# WaterMonitorV7_1.net
KiCad netlist of a schematic drawn in EAGLE
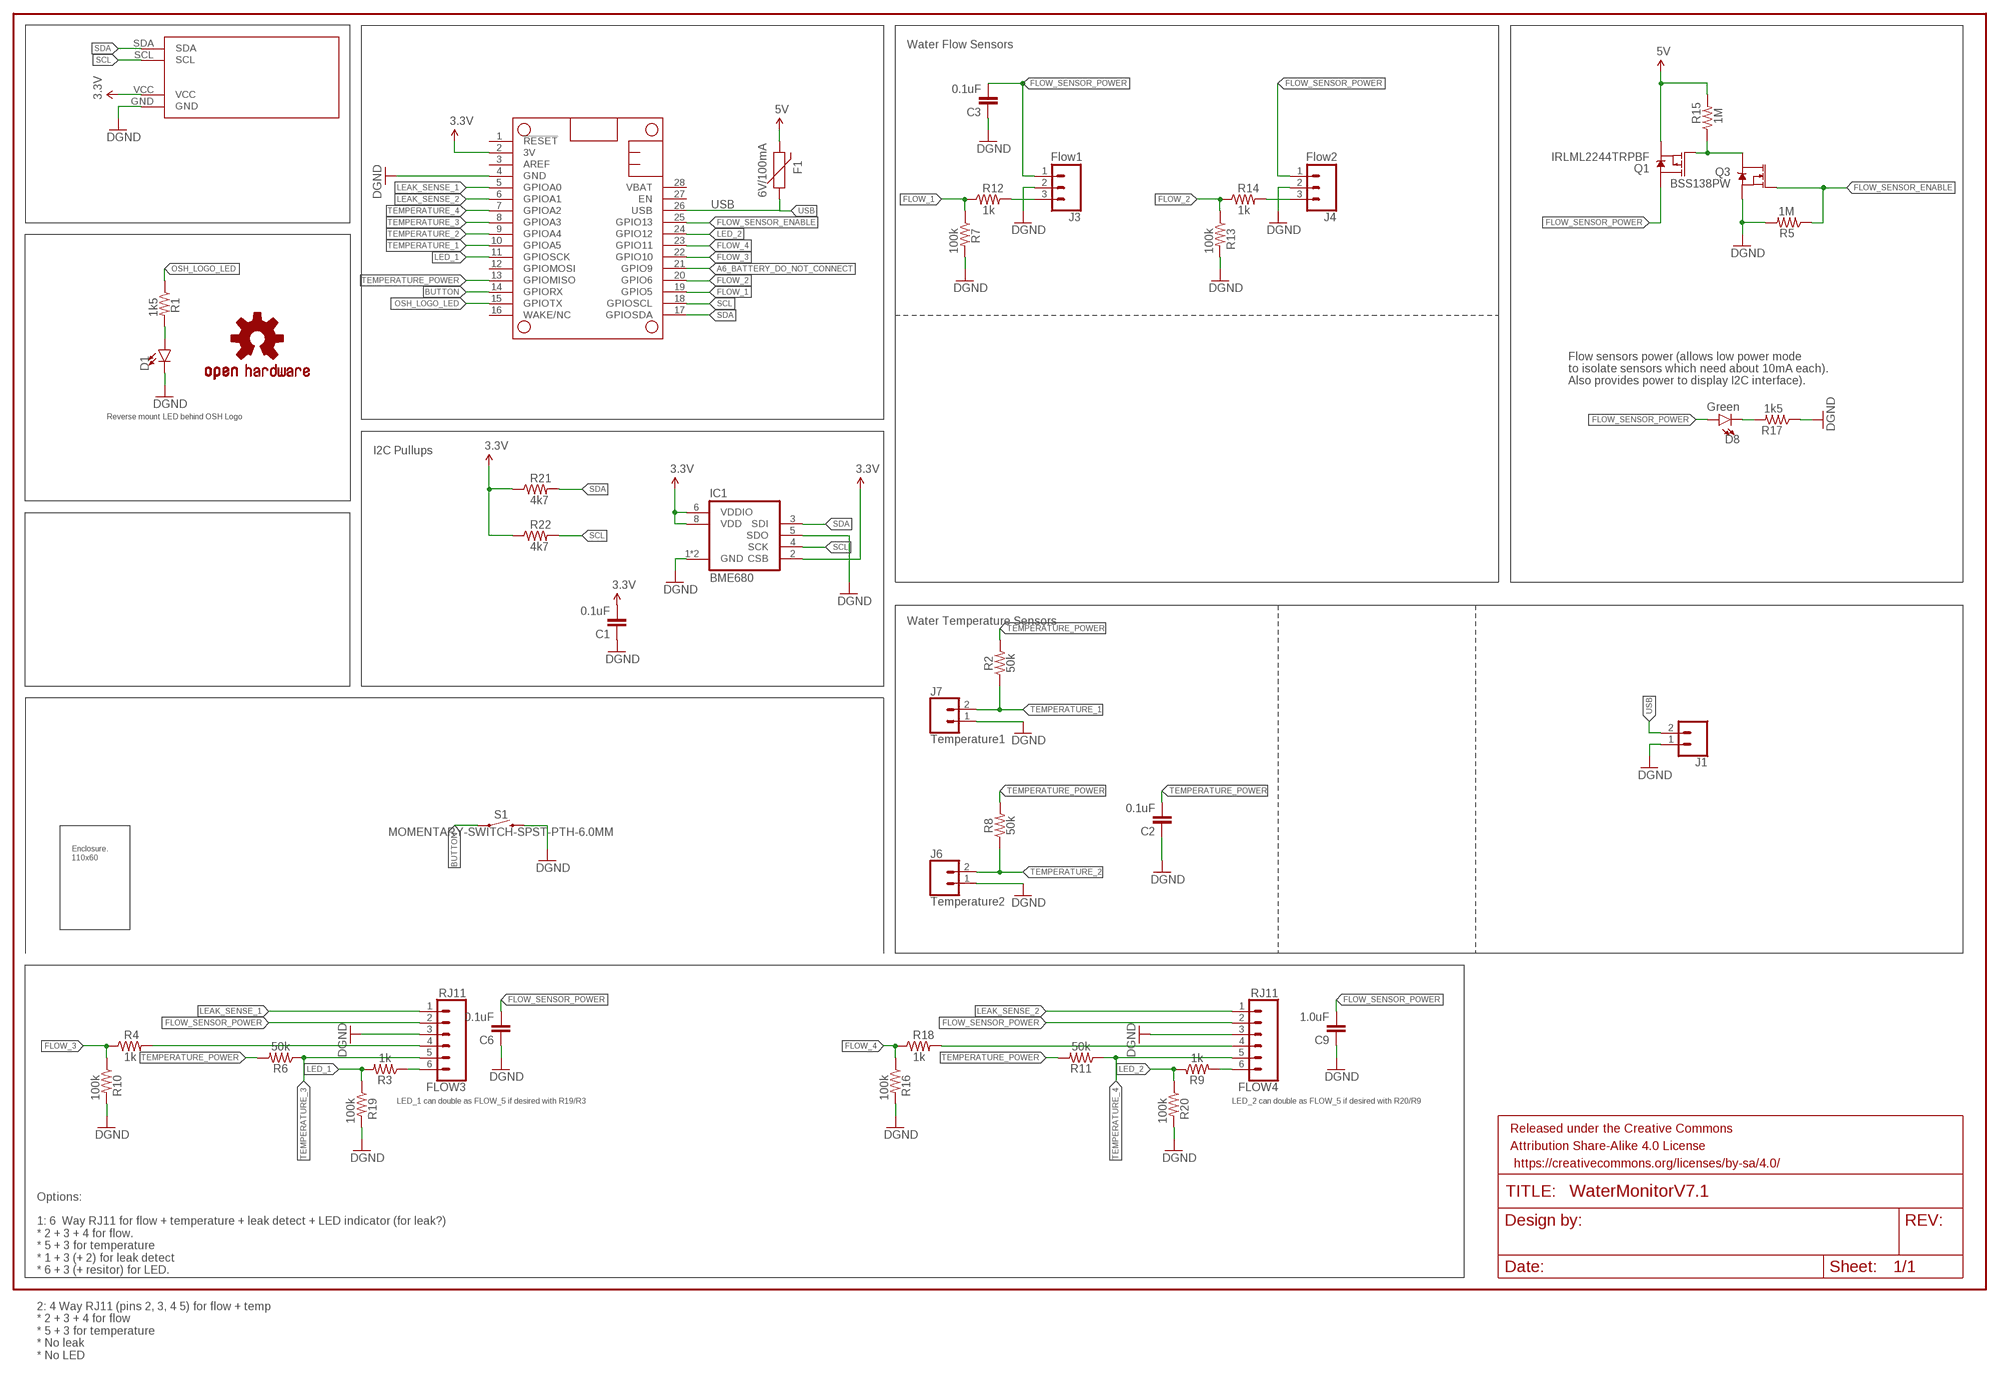
[diagram p0: schematic, sheet 1]

(export (version "E")
  (design (tool "Eeschema 10.0.6"))
  (components
    (comp (ref "C1")
      (value "0.1uF")
      (footprint "eagle-import:0805")
      (libsource (lib "eagle-import") (part "CAP0805"))
    )
    (comp (ref "C2")
      (value "0.1uF")
      (footprint "eagle-import:0805")
      (libsource (lib "eagle-import") (part "CAP0805"))
    )
    (comp (ref "C3")
      (value "0.1uF")
      (footprint "eagle-import:0805")
      (libsource (lib "eagle-import") (part "CAP0805"))
    )
    (comp (ref "C6")
      (value "0.1uF")
      (footprint "eagle-import:0805")
      (libsource (lib "eagle-import") (part "CAP0805"))
    )
    (comp (ref "C9")
      (value "1.0uF")
      (footprint "eagle-import:0805")
      (libsource (lib "eagle-import") (part "CAP0805"))
    )
    (comp (ref "D1")
      (value "LED1206-BOTTOM")
      (footprint "eagle-import:LED-1206-BOTTOM")
      (libsource (lib "eagle-import") (part "LED1206-BOTTOM"))
    )
    (comp (ref "D8")
      (value "Green")
      (footprint "eagle-import:LED-1206")
      (libsource (lib "eagle-import") (part "LED-BLUE1206"))
    )
    (comp (ref "F1")
      (value "6V/100mA")
      (footprint "eagle-import:1206")
      (libsource (lib "eagle-import") (part "PPTC_HALF-AMP"))
    )
    (comp (ref "FLOW3")
      (value "RJ11")
      (footprint "eagle-import:RJ11-6")
      (libsource (lib "eagle-import") (part "RJ11-6"))
    )
    (comp (ref "FLOW4")
      (value "RJ11")
      (footprint "eagle-import:RJ11-6")
      (libsource (lib "eagle-import") (part "RJ11-6"))
    )
    (comp (ref "FRAME2")
      (value "FRAME-LEDGER")
      (footprint "eagle-import:CREATIVE_COMMONS")
      (libsource (lib "eagle-import") (part "FRAME-LEDGER"))
    )
    (comp (ref "IC1")
      (value "BME680")
      (footprint "eagle-import:BME680")
      (libsource (lib "eagle-import") (part "BME680"))
    )
    (comp (ref "J1")
      (value "CONN_02-JST-2MM-SMT")
      (footprint "eagle-import:JST-2-SMD")
      (libsource (lib "eagle-import") (part "CONN_02-JST-2MM-SMT"))
    )
    (comp (ref "J3")
      (value "Flow1")
      (footprint "eagle-import:JST-HX-3-PTH-VERT")
      (libsource (lib "eagle-import") (part "CONN_03JST-HX-PTH-VERT"))
    )
    (comp (ref "J4")
      (value "Flow2")
      (footprint "eagle-import:JST-HX-3-PTH-VERT")
      (libsource (lib "eagle-import") (part "CONN_03JST-HX-PTH-VERT"))
    )
    (comp (ref "J6")
      (value "Temperature2")
      (footprint "eagle-import:MOLEX-1X2")
      (libsource (lib "eagle-import") (part "CONN_02POLAR"))
    )
    (comp (ref "J7")
      (value "Temperature1")
      (footprint "eagle-import:MOLEX-1X2")
      (libsource (lib "eagle-import") (part "CONN_02POLAR"))
    )
    (comp (ref "LOGO1")
      (value "OSHW-LOGOM")
      (footprint "eagle-import:OSHW-LOGO-M")
      (libsource (lib "eagle-import") (part "OSHW-LOGOM"))
    )
    (comp (ref "MS1")
      (value "FEATHERWINGSIMPLE")
      (footprint "eagle-import:FEATHERWING_BREAKOUT_SIMPLE")
      (libsource (lib "eagle-import") (part "FEATHERWINGSIMPLE"))
    )
    (comp (ref "Q1")
      (value "IRLML2244TRPBF")
      (footprint "eagle-import:SOT23-3")
      (libsource (lib "eagle-import") (part "MOSFET_PCH-IRLML2244"))
    )
    (comp (ref "Q3")
      (value "BSS138PW")
      (footprint "eagle-import:SOT23-3")
      (libsource (lib "eagle-import") (part "MOSFET-NCH-BSS138"))
    )
    (comp (ref "R1")
      (value "1k5")
      (footprint "eagle-import:0805")
      (libsource (lib "eagle-import") (part "RESISTOR0805"))
    )
    (comp (ref "R2")
      (value "50k")
      (footprint "eagle-import:0805")
      (libsource (lib "eagle-import") (part "RESISTOR0805"))
    )
    (comp (ref "R3")
      (value "1k")
      (footprint "eagle-import:0805")
      (libsource (lib "eagle-import") (part "RESISTOR0805"))
    )
    (comp (ref "R4")
      (value "1k")
      (footprint "eagle-import:0805")
      (libsource (lib "eagle-import") (part "RESISTOR0805"))
    )
    (comp (ref "R5")
      (value "1M")
      (footprint "eagle-import:0805")
      (libsource (lib "eagle-import") (part "RESISTOR0805"))
    )
    (comp (ref "R6")
      (value "50k")
      (footprint "eagle-import:0805")
      (libsource (lib "eagle-import") (part "RESISTOR0805"))
    )
    (comp (ref "R7")
      (value "100k")
      (footprint "eagle-import:0805")
      (libsource (lib "eagle-import") (part "RESISTOR0805"))
    )
    (comp (ref "R8")
      (value "50k")
      (footprint "eagle-import:0805")
      (libsource (lib "eagle-import") (part "RESISTOR0805"))
    )
    (comp (ref "R9")
      (value "1k")
      (footprint "eagle-import:0805")
      (libsource (lib "eagle-import") (part "RESISTOR0805"))
    )
    (comp (ref "R10")
      (value "100k")
      (footprint "eagle-import:0805")
      (libsource (lib "eagle-import") (part "RESISTOR0805"))
    )
    (comp (ref "R11")
      (value "50k")
      (footprint "eagle-import:0805")
      (libsource (lib "eagle-import") (part "RESISTOR0805"))
    )
    (comp (ref "R12")
      (value "1k")
      (footprint "eagle-import:0805")
      (libsource (lib "eagle-import") (part "RESISTOR0805"))
    )
    (comp (ref "R13")
      (value "100k")
      (footprint "eagle-import:0805")
      (libsource (lib "eagle-import") (part "RESISTOR0805"))
    )
    (comp (ref "R14")
      (value "1k")
      (footprint "eagle-import:0805")
      (libsource (lib "eagle-import") (part "RESISTOR0805"))
    )
    (comp (ref "R15")
      (value "1M")
      (footprint "eagle-import:0805")
      (libsource (lib "eagle-import") (part "RESISTOR0805"))
    )
    (comp (ref "R16")
      (value "100k")
      (footprint "eagle-import:0805")
      (libsource (lib "eagle-import") (part "RESISTOR0805"))
    )
    (comp (ref "R17")
      (value "1k5")
      (footprint "eagle-import:0805")
      (libsource (lib "eagle-import") (part "RESISTOR0805"))
    )
    (comp (ref "R18")
      (value "1k")
      (footprint "eagle-import:0805")
      (libsource (lib "eagle-import") (part "RESISTOR0805"))
    )
    (comp (ref "R19")
      (value "100k")
      (footprint "eagle-import:0805")
      (libsource (lib "eagle-import") (part "RESISTOR0805"))
    )
    (comp (ref "R20")
      (value "100k")
      (footprint "eagle-import:0805")
      (libsource (lib "eagle-import") (part "RESISTOR0805"))
    )
    (comp (ref "R21")
      (value "4k7")
      (footprint "eagle-import:0805")
      (libsource (lib "eagle-import") (part "RESISTOR0805"))
    )
    (comp (ref "R22")
      (value "4k7")
      (footprint "eagle-import:0805")
      (libsource (lib "eagle-import") (part "RESISTOR0805"))
    )
    (comp (ref "S1")
      (value "MOMENTARY-SWITCH-SPST-PTH-6.0MM")
      (footprint "eagle-import:TACTILE_SWITCH_PTH_6.0MM")
      (libsource (lib "eagle-import") (part "MOMENTARY-SWITCH-SPST-PTH-6.0MM"))
    )
    (comp (ref "U$1")
      (value "CAMDENBOSS-ENCLOSURE-110X60BOTH-EXTENDED-WIDE")
      (footprint "eagle-import:CAMDENBOSS_ENCLOSURE_110X60_WIDE_EXTENDED")
      (libsource (lib "eagle-import") (part "CAMDENBOSS-ENCLOSURE-110X60BOTH-EXTENDED-WIDE"))
    )
    (comp (ref "U$2")
      (value "DISPLAY0.96_INCH_DISPLAY")
      (footprint "eagle-import:I2C_DISPLAY_0.96_INCH")
      (libsource (lib "eagle-import") (part "DISPLAY0.96_INCH_DISPLAY"))
    )
  )
  (nets
    (net (code "1") (name "/VBAT") (class "Default")
      (node (ref "MS1") (pin "28") (pinfunction "VBAT_28") (pintype "power_in"))
    )
    (net (code "2") (name "3.3V") (class "Default")
      (node (ref "C1") (pin "2") (pinfunction "2_2") (pintype "passive"))
      (node (ref "IC1") (pin "2") (pinfunction "CSB_2") (pintype "input"))
      (node (ref "IC1") (pin "6") (pinfunction "VDDIO_6") (pintype "power_in"))
      (node (ref "IC1") (pin "8") (pinfunction "VDD_8") (pintype "power_in"))
      (node (ref "MS1") (pin "2") (pinfunction "3V_2") (pintype "power_in"))
      (node (ref "R21") (pin "1") (pinfunction "1_1") (pintype "passive"))
      (node (ref "R22") (pin "1") (pinfunction "1_1") (pintype "passive"))
      (node (ref "U$2") (pin "VCC") (pinfunction "VCC_VCC") (pintype "power_in"))
    )
    (net (code "3") (name "5V") (class "Default")
      (node (ref "F1") (pin "2") (pinfunction "2_2") (pintype "bidirectional"))
      (node (ref "Q1") (pin "2") (pinfunction "S_2") (pintype "bidirectional"))
      (node (ref "R15") (pin "2") (pinfunction "2_2") (pintype "passive"))
    )
    (net (code "4") (name "A6_BATTERY_DO_NOT_CONNECT") (class "Default")
      (node (ref "MS1") (pin "21") (pinfunction "GPIO9_21") (pintype "bidirectional"))
    )
    (net (code "5") (name "BUTTON") (class "Default")
      (node (ref "MS1") (pin "14") (pinfunction "GPIORX_14") (pintype "bidirectional"))
      (node (ref "S1") (pin "1") (pinfunction "1_1") (pintype "passive"))
    )
    (net (code "6") (name "DGND") (class "Default")
      (node (ref "C1") (pin "1") (pinfunction "1_1") (pintype "passive"))
      (node (ref "C2") (pin "1") (pinfunction "1_1") (pintype "passive"))
      (node (ref "C3") (pin "1") (pinfunction "1_1") (pintype "passive"))
      (node (ref "C6") (pin "1") (pinfunction "1_1") (pintype "passive"))
      (node (ref "C9") (pin "1") (pinfunction "1_1") (pintype "passive"))
      (node (ref "D1") (pin "C") (pinfunction "C_C") (pintype "passive"))
      (node (ref "FLOW3") (pin "3") (pinfunction "3_3") (pintype "passive"))
      (node (ref "FLOW4") (pin "3") (pinfunction "3_3") (pintype "passive"))
      (node (ref "IC1") (pin "1") (pinfunction "GND_1") (pintype "power_in"))
      (node (ref "IC1") (pin "5") (pinfunction "SDO_5") (pintype "output"))
      (node (ref "IC1") (pin "7") (pinfunction "GND_7") (pintype "power_in"))
      (node (ref "J1") (pin "1") (pinfunction "2_1") (pintype "passive"))
      (node (ref "J3") (pin "2") (pinfunction "2_2") (pintype "passive"))
      (node (ref "J4") (pin "2") (pinfunction "2_2") (pintype "passive"))
      (node (ref "J6") (pin "1") (pinfunction "1_1") (pintype "passive"))
      (node (ref "J7") (pin "1") (pinfunction "1_1") (pintype "passive"))
      (node (ref "MS1") (pin "4") (pinfunction "GND_4") (pintype "power_in"))
      (node (ref "Q3") (pin "2") (pinfunction "S_2") (pintype "bidirectional"))
      (node (ref "R10") (pin "2") (pinfunction "2_2") (pintype "passive"))
      (node (ref "R13") (pin "2") (pinfunction "2_2") (pintype "passive"))
      (node (ref "R16") (pin "2") (pinfunction "2_2") (pintype "passive"))
      (node (ref "R17") (pin "1") (pinfunction "1_1") (pintype "passive"))
      (node (ref "R19") (pin "2") (pinfunction "2_2") (pintype "passive"))
      (node (ref "R20") (pin "2") (pinfunction "2_2") (pintype "passive"))
      (node (ref "R5") (pin "2") (pinfunction "2_2") (pintype "passive"))
      (node (ref "R7") (pin "2") (pinfunction "2_2") (pintype "passive"))
      (node (ref "S1") (pin "3") (pinfunction "2_3") (pintype "passive"))
      (node (ref "U$2") (pin "GND") (pinfunction "GND_GND") (pintype "power_in"))
    )
    (net (code "7") (name "FLOW_1") (class "Default")
      (node (ref "MS1") (pin "19") (pinfunction "GPIO5_19") (pintype "bidirectional"))
      (node (ref "R12") (pin "1") (pinfunction "1_1") (pintype "passive"))
      (node (ref "R7") (pin "1") (pinfunction "1_1") (pintype "passive"))
    )
    (net (code "8") (name "FLOW_2") (class "Default")
      (node (ref "MS1") (pin "20") (pinfunction "GPIO6_20") (pintype "bidirectional"))
      (node (ref "R13") (pin "1") (pinfunction "1_1") (pintype "passive"))
      (node (ref "R14") (pin "1") (pinfunction "1_1") (pintype "passive"))
    )
    (net (code "9") (name "FLOW_3") (class "Default")
      (node (ref "MS1") (pin "22") (pinfunction "GPIO10_22") (pintype "bidirectional"))
      (node (ref "R10") (pin "1") (pinfunction "1_1") (pintype "passive"))
      (node (ref "R4") (pin "1") (pinfunction "1_1") (pintype "passive"))
    )
    (net (code "10") (name "FLOW_4") (class "Default")
      (node (ref "MS1") (pin "23") (pinfunction "GPIO11_23") (pintype "bidirectional"))
      (node (ref "R16") (pin "1") (pinfunction "1_1") (pintype "passive"))
      (node (ref "R18") (pin "1") (pinfunction "1_1") (pintype "passive"))
    )
    (net (code "11") (name "FLOW_SENSOR_ENABLE") (class "Default")
      (node (ref "MS1") (pin "25") (pinfunction "GPIO13_25") (pintype "bidirectional"))
      (node (ref "Q3") (pin "1") (pinfunction "G_1") (pintype "bidirectional"))
      (node (ref "R5") (pin "1") (pinfunction "1_1") (pintype "passive"))
    )
    (net (code "12") (name "FLOW_SENSOR_POWER") (class "Default")
      (node (ref "C3") (pin "2") (pinfunction "2_2") (pintype "passive"))
      (node (ref "C6") (pin "2") (pinfunction "2_2") (pintype "passive"))
      (node (ref "C9") (pin "2") (pinfunction "2_2") (pintype "passive"))
      (node (ref "D8") (pin "A") (pinfunction "A_A") (pintype "passive"))
      (node (ref "FLOW3") (pin "2") (pinfunction "2_2") (pintype "passive"))
      (node (ref "FLOW4") (pin "2") (pinfunction "2_2") (pintype "passive"))
      (node (ref "J3") (pin "1") (pinfunction "1_1") (pintype "passive"))
      (node (ref "J4") (pin "1") (pinfunction "1_1") (pintype "passive"))
      (node (ref "Q1") (pin "3") (pinfunction "D_3") (pintype "bidirectional"))
    )
    (net (code "13") (name "LEAK_SENSE_1") (class "Default")
      (node (ref "FLOW3") (pin "1") (pinfunction "1_1") (pintype "passive"))
      (node (ref "MS1") (pin "5") (pinfunction "GPIOA0_5") (pintype "bidirectional"))
    )
    (net (code "14") (name "LEAK_SENSE_2") (class "Default")
      (node (ref "FLOW4") (pin "1") (pinfunction "1_1") (pintype "passive"))
      (node (ref "MS1") (pin "6") (pinfunction "GPIOA1_6") (pintype "bidirectional"))
    )
    (net (code "15") (name "LED_1") (class "Default")
      (node (ref "MS1") (pin "11") (pinfunction "GPIOSCK_11") (pintype "bidirectional"))
      (node (ref "R19") (pin "1") (pinfunction "1_1") (pintype "passive"))
      (node (ref "R3") (pin "2") (pinfunction "2_2") (pintype "passive"))
    )
    (net (code "16") (name "LED_2") (class "Default")
      (node (ref "MS1") (pin "24") (pinfunction "GPIO12_24") (pintype "bidirectional"))
      (node (ref "R20") (pin "1") (pinfunction "1_1") (pintype "passive"))
      (node (ref "R9") (pin "1") (pinfunction "1_1") (pintype "passive"))
    )
    (net (code "17") (name "Net-(D1-PadA)") (class "Default")
      (node (ref "D1") (pin "A") (pinfunction "A_A") (pintype "passive"))
      (node (ref "R1") (pin "2") (pinfunction "2_2") (pintype "passive"))
    )
    (net (code "18") (name "Net-(D8-PadC)") (class "Default")
      (node (ref "D8") (pin "C") (pinfunction "C_C") (pintype "passive"))
      (node (ref "R17") (pin "2") (pinfunction "2_2") (pintype "passive"))
    )
    (net (code "19") (name "Net-(FLOW3-Pad4)") (class "Default")
      (node (ref "FLOW3") (pin "4") (pinfunction "4_4") (pintype "passive"))
      (node (ref "R4") (pin "2") (pinfunction "2_2") (pintype "passive"))
    )
    (net (code "20") (name "Net-(FLOW3-Pad6)") (class "Default")
      (node (ref "FLOW3") (pin "6") (pinfunction "6_6") (pintype "passive"))
      (node (ref "R3") (pin "1") (pinfunction "1_1") (pintype "passive"))
    )
    (net (code "21") (name "Net-(FLOW4-Pad4)") (class "Default")
      (node (ref "FLOW4") (pin "4") (pinfunction "4_4") (pintype "passive"))
      (node (ref "R18") (pin "2") (pinfunction "2_2") (pintype "passive"))
    )
    (net (code "22") (name "Net-(FLOW4-Pad6)") (class "Default")
      (node (ref "FLOW4") (pin "6") (pinfunction "6_6") (pintype "passive"))
      (node (ref "R9") (pin "2") (pinfunction "2_2") (pintype "passive"))
    )
    (net (code "23") (name "Net-(J3-Pad3)") (class "Default")
      (node (ref "J3") (pin "3") (pinfunction "3_3") (pintype "passive"))
      (node (ref "R12") (pin "2") (pinfunction "2_2") (pintype "passive"))
    )
    (net (code "24") (name "Net-(J4-Pad3)") (class "Default")
      (node (ref "J4") (pin "3") (pinfunction "3_3") (pintype "passive"))
      (node (ref "R14") (pin "2") (pinfunction "2_2") (pintype "passive"))
    )
    (net (code "25") (name "Net-(Q1-G)") (class "Default")
      (node (ref "Q1") (pin "1") (pinfunction "G_1") (pintype "bidirectional"))
      (node (ref "Q3") (pin "3") (pinfunction "D_3") (pintype "bidirectional"))
      (node (ref "R15") (pin "1") (pinfunction "1_1") (pintype "passive"))
    )
    (net (code "26") (name "OSH_LOGO_LED") (class "Default")
      (node (ref "MS1") (pin "15") (pinfunction "GPIOTX_15") (pintype "bidirectional"))
      (node (ref "R1") (pin "1") (pinfunction "1_1") (pintype "passive"))
    )
    (net (code "27") (name "SCL") (class "Default")
      (node (ref "IC1") (pin "4") (pinfunction "SCK_4") (pintype "input"))
      (node (ref "MS1") (pin "18") (pinfunction "GPIOSCL_18") (pintype "bidirectional"))
      (node (ref "R22") (pin "2") (pinfunction "2_2") (pintype "passive"))
      (node (ref "U$2") (pin "SCL") (pinfunction "SCL_SCL") (pintype "bidirectional"))
    )
    (net (code "28") (name "SDA") (class "Default")
      (node (ref "IC1") (pin "3") (pinfunction "SDI_3") (pintype "input"))
      (node (ref "MS1") (pin "17") (pinfunction "GPIOSDA_17") (pintype "bidirectional"))
      (node (ref "R21") (pin "2") (pinfunction "2_2") (pintype "passive"))
      (node (ref "U$2") (pin "SDA") (pinfunction "SDA_SDA") (pintype "bidirectional"))
    )
    (net (code "29") (name "TEMPERATURE_1") (class "Default")
      (node (ref "J7") (pin "2") (pinfunction "2_2") (pintype "passive"))
      (node (ref "MS1") (pin "10") (pinfunction "GPIOA5_10") (pintype "bidirectional"))
      (node (ref "R2") (pin "1") (pinfunction "1_1") (pintype "passive"))
    )
    (net (code "30") (name "TEMPERATURE_2") (class "Default")
      (node (ref "J6") (pin "2") (pinfunction "2_2") (pintype "passive"))
      (node (ref "MS1") (pin "9") (pinfunction "GPIOA4_9") (pintype "bidirectional"))
      (node (ref "R8") (pin "1") (pinfunction "1_1") (pintype "passive"))
    )
    (net (code "31") (name "TEMPERATURE_3") (class "Default")
      (node (ref "FLOW3") (pin "5") (pinfunction "5_5") (pintype "passive"))
      (node (ref "MS1") (pin "8") (pinfunction "GPIOA3_8") (pintype "bidirectional"))
      (node (ref "R6") (pin "1") (pinfunction "1_1") (pintype "passive"))
    )
    (net (code "32") (name "TEMPERATURE_4") (class "Default")
      (node (ref "FLOW4") (pin "5") (pinfunction "5_5") (pintype "passive"))
      (node (ref "MS1") (pin "7") (pinfunction "GPIOA2_7") (pintype "bidirectional"))
      (node (ref "R11") (pin "1") (pinfunction "1_1") (pintype "passive"))
    )
    (net (code "33") (name "TEMPERATURE_POWER") (class "Default")
      (node (ref "C2") (pin "2") (pinfunction "2_2") (pintype "passive"))
      (node (ref "MS1") (pin "13") (pinfunction "GPIOMISO_13") (pintype "bidirectional"))
      (node (ref "R11") (pin "2") (pinfunction "2_2") (pintype "passive"))
      (node (ref "R2") (pin "2") (pinfunction "2_2") (pintype "passive"))
      (node (ref "R6") (pin "2") (pinfunction "2_2") (pintype "passive"))
      (node (ref "R8") (pin "2") (pinfunction "2_2") (pintype "passive"))
    )
    (net (code "34") (name "USB") (class "Default")
      (node (ref "F1") (pin "1") (pinfunction "1_1") (pintype "bidirectional"))
      (node (ref "J1") (pin "2") (pinfunction "1_2") (pintype "passive"))
      (node (ref "MS1") (pin "26") (pinfunction "USB_26") (pintype "power_in"))
    )
    (net (code "35") (name "unconnected-(MS1-AREF-Pad3)") (class "Default")
      (node (ref "MS1") (pin "3") (pinfunction "AREF_3") (pintype "passive"))
    )
    (net (code "36") (name "unconnected-(MS1-EN-Pad27)") (class "Default")
      (node (ref "MS1") (pin "27") (pinfunction "EN_27") (pintype "passive"))
    )
    (net (code "37") (name "unconnected-(MS1-GPIOMOSI-Pad12)") (class "Default")
      (node (ref "MS1") (pin "12") (pinfunction "GPIOMOSI_12") (pintype "bidirectional"))
    )
    (net (code "38") (name "unconnected-(MS1-WAKE{slash}NC-Pad16)") (class "Default")
      (node (ref "MS1") (pin "16") (pinfunction "WAKE/NC_16") (pintype "passive"))
    )
    (net (code "39") (name "unconnected-(MS1-~{RESET}-Pad1)") (class "Default")
      (node (ref "MS1") (pin "1") (pinfunction "~{RESET}_1") (pintype "input"))
    )
  )
)
